# Microcrontroller.net
KiCad netlist of a schematic drawn in Altium Designer
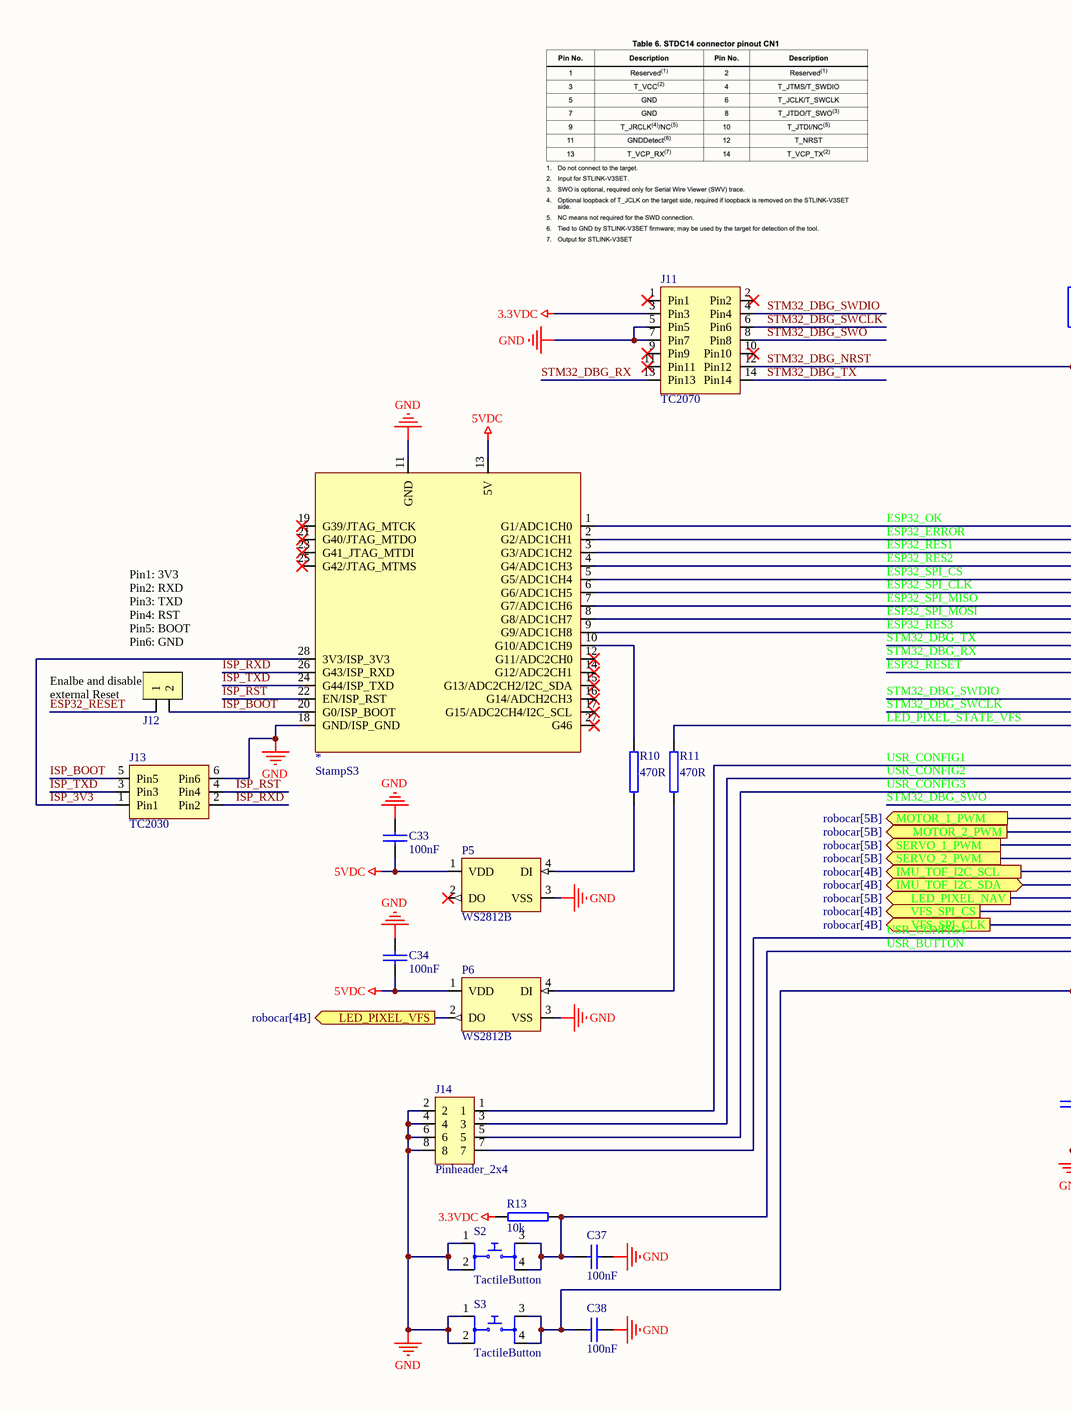
[diagram p0: Microcrontroller.SchDoc, left]
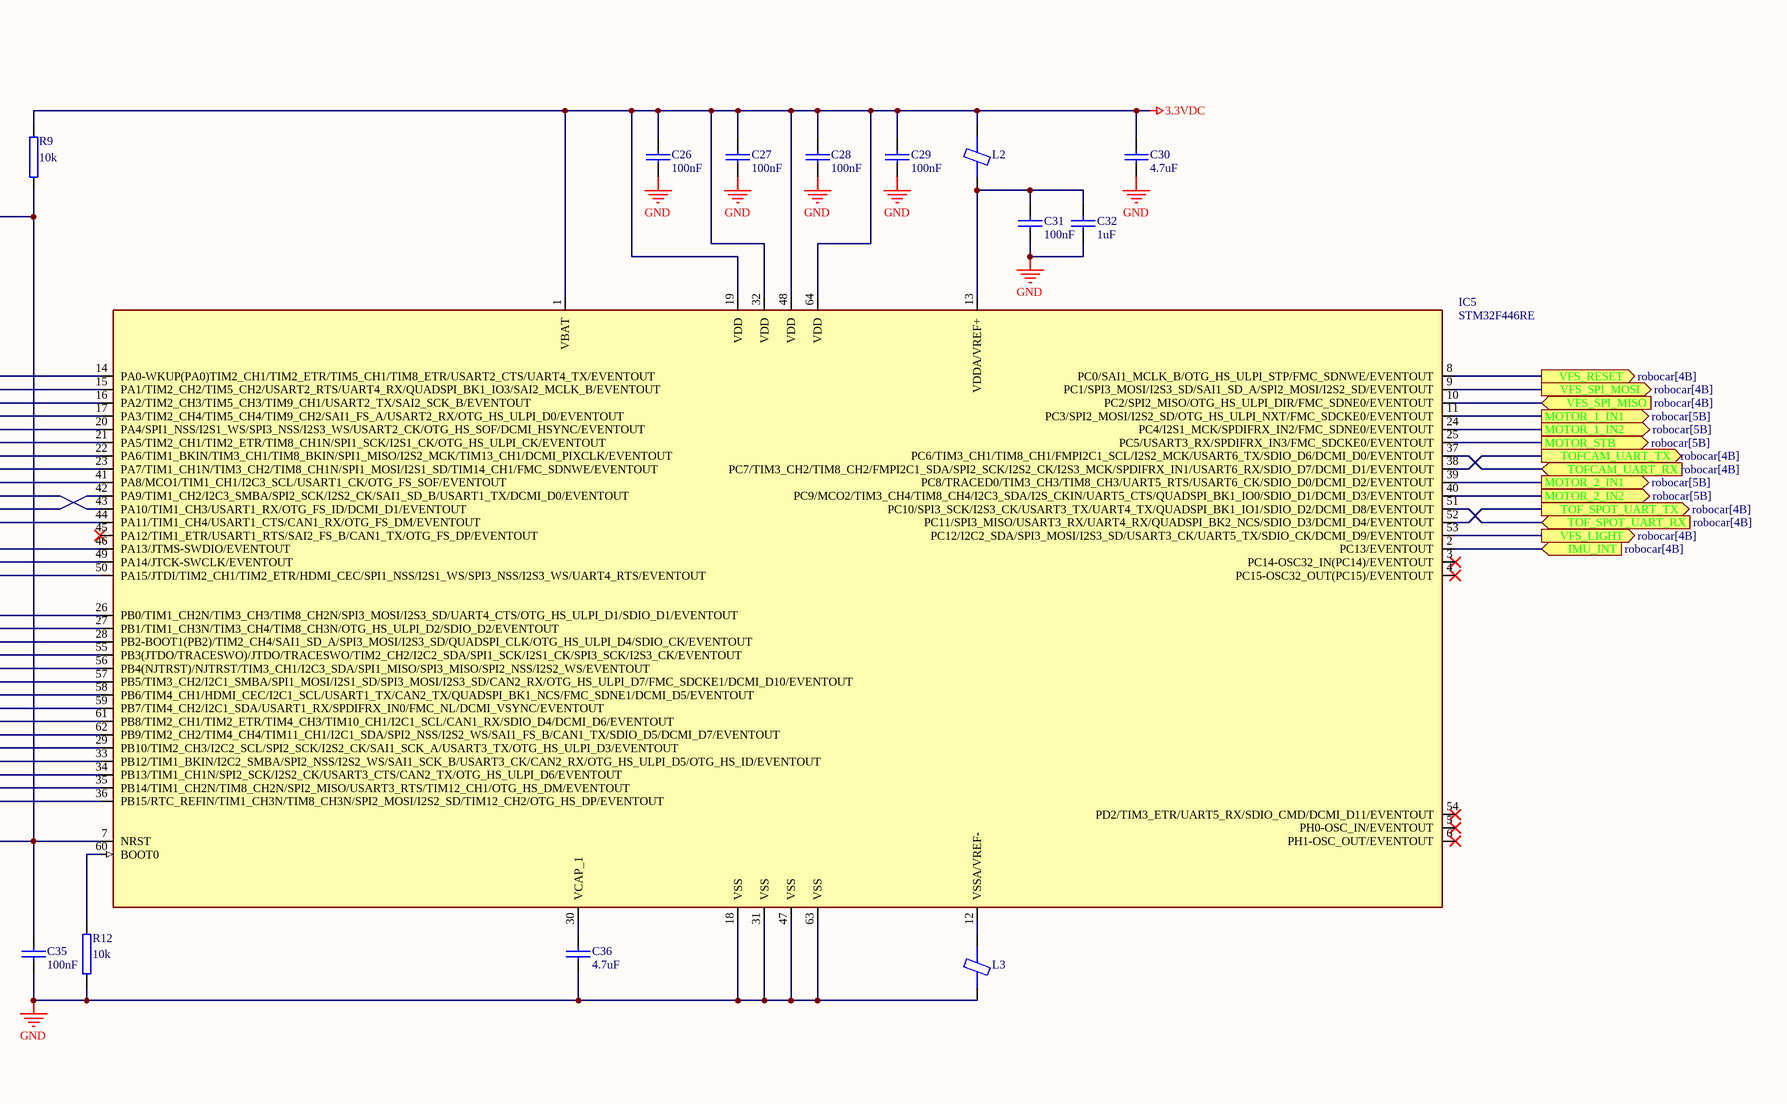
[diagram p1: Microcrontroller.SchDoc, right]

(export (version "E")
  (design (tool "Eeschema 10.0.6"))
  (components
    (comp (ref "*")
      (value "StampS3")
      (footprint "Stamp-S3-SMD")
      (libsource (lib "M5Stack_StampS3") (part "StampS3"))
    )
    (comp (ref "C26")
      (value "100nF")
      (footprint "0603")
      (fields
        (field (name "TOLERANCE") "-20%/+80%")
        (field (name "VOLTAGE") "50V")
        (field (name "Comment") "C 100nF 0603")
      )
      (libsource (lib "FHGR_Altium_database") (part "Capacitor"))
    )
    (comp (ref "C27")
      (value "100nF")
      (footprint "0603")
      (fields
        (field (name "TOLERANCE") "-20%/+80%")
        (field (name "VOLTAGE") "50V")
        (field (name "Comment") "C 100nF 0603")
      )
      (libsource (lib "FHGR_Altium_database") (part "Capacitor"))
    )
    (comp (ref "C28")
      (value "100nF")
      (footprint "0603")
      (fields
        (field (name "TOLERANCE") "-20%/+80%")
        (field (name "VOLTAGE") "50V")
        (field (name "Comment") "C 100nF 0603")
      )
      (libsource (lib "FHGR_Altium_database") (part "Capacitor"))
    )
    (comp (ref "C29")
      (value "100nF")
      (footprint "0603")
      (fields
        (field (name "TOLERANCE") "-20%/+80%")
        (field (name "VOLTAGE") "50V")
        (field (name "Comment") "C 100nF 0603")
      )
      (libsource (lib "FHGR_Altium_database") (part "Capacitor"))
    )
    (comp (ref "C30")
      (value "4.7uF")
      (footprint "0603")
      (fields
        (field (name "TOLERANCE") "10%")
        (field (name "VOLTAGE") "6.3V")
        (field (name "Comment") "C 4.7uF 0603")
      )
      (libsource (lib "FHGR_Altium_database") (part "Capacitor"))
    )
    (comp (ref "C31")
      (value "100nF")
      (footprint "0603")
      (fields
        (field (name "TOLERANCE") "-20%/+80%")
        (field (name "VOLTAGE") "50V")
        (field (name "Comment") "C 100nF 0603")
      )
      (libsource (lib "FHGR_Altium_database") (part "Capacitor"))
    )
    (comp (ref "C32")
      (value "1uF")
      (footprint "0603")
      (fields
        (field (name "TOLERANCE") "10%")
        (field (name "VOLTAGE") "25V")
        (field (name "Comment") "C 1uF 0603")
      )
      (libsource (lib "FHGR_Altium_database") (part "Capacitor"))
    )
    (comp (ref "C33")
      (value "100nF")
      (footprint "0603")
      (fields
        (field (name "TOLERANCE") "-20%/+80%")
        (field (name "VOLTAGE") "50V")
        (field (name "Comment") "C 100nF 0603")
      )
      (libsource (lib "FHGR_Altium_database") (part "Capacitor"))
    )
    (comp (ref "C34")
      (value "100nF")
      (footprint "0603")
      (fields
        (field (name "TOLERANCE") "-20%/+80%")
        (field (name "VOLTAGE") "50V")
        (field (name "Comment") "C 100nF 0603")
      )
      (libsource (lib "FHGR_Altium_database") (part "Capacitor"))
    )
    (comp (ref "C35")
      (value "100nF")
      (footprint "0603")
      (fields
        (field (name "TOLERANCE") "-20%/+80%")
        (field (name "VOLTAGE") "50V")
        (field (name "Comment") "C 100nF 0603")
      )
      (libsource (lib "FHGR_Altium_database") (part "Capacitor"))
    )
    (comp (ref "C36")
      (value "4.7uF")
      (footprint "0603")
      (fields
        (field (name "TOLERANCE") "10%")
        (field (name "VOLTAGE") "6.3V")
        (field (name "Comment") "C 4.7uF 0603")
      )
      (libsource (lib "FHGR_Altium_database") (part "Capacitor"))
    )
    (comp (ref "C37")
      (value "100nF")
      (footprint "0603")
      (fields
        (field (name "TOLERANCE") "-20%/+80%")
        (field (name "VOLTAGE") "50V")
        (field (name "Comment") "C 100nF 0603")
      )
      (libsource (lib "FHGR_Altium_database") (part "Capacitor"))
    )
    (comp (ref "C38")
      (value "100nF")
      (footprint "0603")
      (fields
        (field (name "TOLERANCE") "-20%/+80%")
        (field (name "VOLTAGE") "50V")
        (field (name "Comment") "C 100nF 0603")
      )
      (libsource (lib "FHGR_Altium_database") (part "Capacitor"))
    )
    (comp (ref "IC5")
      (value "STM32F446RE")
      (footprint "STM32F446RET6")
      (libsource (lib "STM32F446RE") (part "STM32F446RE"))
    )
    (comp (ref "J11") (value "TC2070") (footprint "TC2070") (libsource (lib "Tag-Connect") (part "TC2070")))
    (comp (ref "J12")
      (value "2Pin_Male")
      (footprint "Header1x2_254")
      (libsource (lib "FHGR_Altium_database") (part "Connector2Pin"))
    )
    (comp (ref "J13") (value "TC2030") (footprint "TC2030") (libsource (lib "Tag-Connect") (part "TC2030")))
    (comp (ref "J14")
      (value "Pinheader_2x4")
      (footprint "61300821121")
      (libsource (lib "util") (part "Pinheader_2x4"))
    )
    (comp (ref "L2")
      (value "L Ferrit Bead")
      (footprint "0805")
      (libsource (lib "FHGR_Altium_database") (part "Bead"))
    )
    (comp (ref "L3")
      (value "L Ferrit Bead")
      (footprint "0805")
      (libsource (lib "FHGR_Altium_database") (part "Bead"))
    )
    (comp (ref "P5")
      (value "WS2812B")
      (footprint "WS2812B_SMD")
      (libsource (lib "NeoPixel") (part "WS2812B"))
    )
    (comp (ref "P6")
      (value "WS2812B")
      (footprint "WS2812B_SMD")
      (libsource (lib "NeoPixel") (part "WS2812B"))
    )
    (comp (ref "R9")
      (value "10k")
      (footprint "0805")
      (fields (field (name "TOLERANCE") "1%") (field (name "Comment") "R 10K 0805"))
      (libsource (lib "FHGR_Altium_database") (part "Resistor"))
    )
    (comp (ref "R10")
      (value "470R")
      (footprint "0805")
      (fields (field (name "TOLERANCE") "1%") (field (name "Comment") "R 220R 0805"))
      (libsource (lib "FHGR_Altium_database") (part "Resistor"))
    )
    (comp (ref "R11")
      (value "470R")
      (footprint "0805")
      (fields (field (name "TOLERANCE") "1%") (field (name "Comment") "R 220R 0805"))
      (libsource (lib "FHGR_Altium_database") (part "Resistor"))
    )
    (comp (ref "R12")
      (value "10k")
      (footprint "0805")
      (fields (field (name "TOLERANCE") "1%") (field (name "Comment") "R 10K 0805"))
      (libsource (lib "FHGR_Altium_database") (part "Resistor"))
    )
    (comp (ref "R13")
      (value "10k")
      (footprint "0805")
      (fields (field (name "TOLERANCE") "1%") (field (name "Comment") "R 10K 0805"))
      (libsource (lib "FHGR_Altium_database") (part "Resistor"))
    )
    (comp (ref "S2")
      (value "TactileButton")
      (footprint "TactileButton-6x6mm")
      (fields (field (name "VOLTAGE") "12V"))
      (libsource (lib "FHGR_Altium_database") (part "Switch_Press_Button_4PIN"))
    )
    (comp (ref "S3")
      (value "TactileButton")
      (footprint "TactileButton-6x6mm")
      (fields (field (name "VOLTAGE") "12V"))
      (libsource (lib "FHGR_Altium_database") (part "Switch_Press_Button_4PIN"))
    )
  )
  (nets
    (net (code "1") (name "/ESP32_ERROR") (class "Default")
      (node (ref "*") (pin "2") (pinfunction "G2/ADC1CH1_2") (pintype "passive"))
      (node (ref "IC5") (pin "15") (pinfunction "PA1/TIM2_CH2/TIM5_CH2/USART2_RTS/UART4_RX/QUADSPI_BK1_IO3/SAI2_MCLK_B/EVENTOUT_15") (pintype "bidirectional"))
    )
    (net (code "2") (name "/ESP32_OK") (class "Default")
      (node (ref "*") (pin "1") (pinfunction "G1/ADC1CH0_1") (pintype "passive"))
      (node (ref "IC5") (pin "14") (pinfunction "PA0-WKUP(PA0)TIM2_CH1/TIM2_ETR/TIM5_CH1/TIM8_ETR/USART2_CTS/UART4_TX/EVENTOUT_14") (pintype "bidirectional"))
    )
    (net (code "3") (name "/ESP32_RES1") (class "Default")
      (node (ref "*") (pin "3") (pinfunction "G3/ADC1CH2_3") (pintype "passive"))
      (node (ref "IC5") (pin "16") (pinfunction "PA2/TIM2_CH3/TIM5_CH3/TIM9_CH1/USART2_TX/SAI2_SCK_B/EVENTOUT_16") (pintype "bidirectional"))
    )
    (net (code "4") (name "/ESP32_RES2") (class "Default")
      (node (ref "*") (pin "4") (pinfunction "G4/ADC1CH3_4") (pintype "passive"))
      (node (ref "IC5") (pin "17") (pinfunction "PA3/TIM2_CH4/TIM5_CH4/TIM9_CH2/SAI1_FS_A/USART2_RX/OTG_HS_ULPI_D0/EVENTOUT_17") (pintype "bidirectional"))
    )
    (net (code "5") (name "/ESP32_RES3") (class "Default")
      (node (ref "*") (pin "9") (pinfunction "G9/ADC1CH8_9") (pintype "passive"))
      (node (ref "IC5") (pin "41") (pinfunction "PA8/MCO1/TIM1_CH1/I2C3_SCL/USART1_CK/OTG_FS_SOF/EVENTOUT_41") (pintype "bidirectional"))
    )
    (net (code "6") (name "/ESP32_RESET") (class "Default")
      (node (ref "IC5") (pin "44") (pinfunction "PA11/TIM1_CH4/USART1_CTS/CAN1_RX/OTG_FS_DM/EVENTOUT_44") (pintype "bidirectional"))
      (node (ref "J12") (pin "1") (pinfunction "1_1") (pintype "passive"))
    )
    (net (code "7") (name "/ESP32_SPI_CLK") (class "Default")
      (node (ref "*") (pin "6") (pinfunction "G6/ADC1CH5_6") (pintype "passive"))
      (node (ref "IC5") (pin "21") (pinfunction "PA5/TIM2_CH1/TIM2_ETR/TIM8_CH1N/SPI1_SCK/I2S1_CK/OTG_HS_ULPI_CK/EVENTOUT_21") (pintype "bidirectional"))
    )
    (net (code "8") (name "/ESP32_SPI_CS") (class "Default")
      (node (ref "*") (pin "5") (pinfunction "G5/ADC1CH4_5") (pintype "passive"))
      (node (ref "IC5") (pin "20") (pinfunction "PA4/SPI1_NSS/I2S1_WS/SPI3_NSS/I2S3_WS/USART2_CK/OTG_HS_SOF/DCMI_HSYNC/EVENTOUT_20") (pintype "bidirectional"))
    )
    (net (code "9") (name "/ESP32_SPI_MISO") (class "Default")
      (node (ref "*") (pin "7") (pinfunction "G7/ADC1CH6_7") (pintype "passive"))
      (node (ref "IC5") (pin "22") (pinfunction "PA6/TIM1_BKIN/TIM3_CH1/TIM8_BKIN/SPI1_MISO/I2S2_MCK/TIM13_CH1/DCMI_PIXCLK/EVENTOUT_22") (pintype "bidirectional"))
    )
    (net (code "10") (name "/ESP32_SPI_MOSI") (class "Default")
      (node (ref "*") (pin "8") (pinfunction "G8/ADC1CH7_8") (pintype "passive"))
      (node (ref "IC5") (pin "23") (pinfunction "PA7/TIM1_CH1N/TIM3_CH2/TIM8_CH1N/SPI1_MOSI/I2S1_SD/TIM14_CH1/FMC_SDNWE/EVENTOUT_23") (pintype "bidirectional"))
    )
    (net (code "11") (name "/IMU_INT") (class "Default")
      (node (ref "IC5") (pin "2") (pinfunction "PC13/EVENTOUT_2") (pintype "bidirectional"))
    )
    (net (code "12") (name "/IMU_TOF_I2C_SCL") (class "Default")
      (node (ref "IC5") (pin "61") (pinfunction "PB8/TIM2_CH1/TIM2_ETR/TIM4_CH3/TIM10_CH1/I2C1_SCL/CAN1_RX/SDIO_D4/DCMI_D6/EVENTOUT_61") (pintype "bidirectional"))
    )
    (net (code "13") (name "/IMU_TOF_I2C_SDA") (class "Default")
      (node (ref "IC5") (pin "62") (pinfunction "PB9/TIM2_CH2/TIM4_CH4/TIM11_CH1/I2C1_SDA/SPI2_NSS/I2S2_WS/SAI1_FS_B/CAN1_TX/SDIO_D5/DCMI_D7/EVENTOUT_62") (pintype "bidirectional"))
    )
    (net (code "14") (name "/ISP_3V3") (class "Default")
      (node (ref "*") (pin "28") (pinfunction "3V3/ISP_3V3_28") (pintype "passive"))
      (node (ref "J13") (pin "1") (pinfunction "Pin1_1") (pintype "passive"))
    )
    (net (code "15") (name "/ISP_BOOT") (class "Default")
      (node (ref "*") (pin "20") (pinfunction "G0/ISP_BOOT_20") (pintype "passive"))
      (node (ref "J12") (pin "2") (pinfunction "2_2") (pintype "passive"))
      (node (ref "J13") (pin "5") (pinfunction "Pin5_5") (pintype "passive"))
    )
    (net (code "16") (name "/ISP_RST") (class "Default")
      (node (ref "*") (pin "22") (pinfunction "EN/ISP_RST_22") (pintype "passive"))
      (node (ref "J13") (pin "4") (pinfunction "Pin4_4") (pintype "passive"))
    )
    (net (code "17") (name "/ISP_RXD") (class "Default")
      (node (ref "*") (pin "26") (pinfunction "G43/ISP_RXD_26") (pintype "passive"))
      (node (ref "J13") (pin "2") (pinfunction "Pin2_2") (pintype "passive"))
    )
    (net (code "18") (name "/ISP_TXD") (class "Default")
      (node (ref "*") (pin "24") (pinfunction "G44/ISP_TXD_24") (pintype "passive"))
      (node (ref "J13") (pin "3") (pinfunction "Pin3_3") (pintype "passive"))
    )
    (net (code "19") (name "/LED_PIXEL_NAV") (class "Default")
      (node (ref "IC5") (pin "29") (pinfunction "PB10/TIM2_CH3/I2C2_SCL/SPI2_SCK/I2S2_CK/SAI1_SCK_A/USART3_TX/OTG_HS_ULPI_D3/EVENTOUT_29") (pintype "bidirectional"))
    )
    (net (code "20") (name "/LED_PIXEL_STATE_VFS") (class "Default")
      (node (ref "IC5") (pin "50") (pinfunction "PA15/JTDI/TIM2_CH1/TIM2_ETR/HDMI_CEC/SPI1_NSS/I2S1_WS/SPI3_NSS/I2S3_WS/UART4_RTS/EVENTOUT_50") (pintype "bidirectional"))
      (node (ref "R11") (pin "2") (pintype "passive"))
    )
    (net (code "21") (name "/LED_PIXEL_VFS") (class "Default")
      (node (ref "P6") (pin "2") (pinfunction "DO_2") (pintype "output"))
    )
    (net (code "22") (name "/MOTOR_1_IN1") (class "Default")
      (node (ref "IC5") (pin "11") (pinfunction "PC3/SPI2_MOSI/I2S2_SD/OTG_HS_ULPI_NXT/FMC_SDCKE0/EVENTOUT_11") (pintype "bidirectional"))
    )
    (net (code "23") (name "/MOTOR_1_IN2") (class "Default")
      (node (ref "IC5") (pin "24") (pinfunction "PC4/I2S1_MCK/SPDIFRX_IN2/FMC_SDNE0/EVENTOUT_24") (pintype "bidirectional"))
    )
    (net (code "24") (name "/MOTOR_1_PWM") (class "Default")
      (node (ref "IC5") (pin "56") (pinfunction "PB4(NJTRST)/NJTRST/TIM3_CH1/I2C3_SDA/SPI1_MISO/SPI3_MISO/SPI2_NSS/I2S2_WS/EVENTOUT_56") (pintype "bidirectional"))
    )
    (net (code "25") (name "/MOTOR_2_IN1") (class "Default")
      (node (ref "IC5") (pin "39") (pinfunction "PC8/TRACED0/TIM3_CH3/TIM8_CH3/UART5_RTS/USART6_CK/SDIO_D0/DCMI_D2/EVENTOUT_39") (pintype "bidirectional"))
    )
    (net (code "26") (name "/MOTOR_2_IN2") (class "Default")
      (node (ref "IC5") (pin "40") (pinfunction "PC9/MCO2/TIM3_CH4/TIM8_CH4/I2C3_SDA/I2S_CKIN/UART5_CTS/QUADSPI_BK1_IO0/SDIO_D1/DCMI_D3/EVENTOUT_40") (pintype "bidirectional"))
    )
    (net (code "27") (name "/MOTOR_2_PWM") (class "Default")
      (node (ref "IC5") (pin "57") (pinfunction "PB5/TIM3_CH2/I2C1_SMBA/SPI1_MOSI/I2S1_SD/SPI3_MOSI/I2S3_SD/CAN2_RX/OTG_HS_ULPI_D7/FMC_SDCKE1/DCMI_D10/EVENTOUT_57") (pintype "bidirectional"))
    )
    (net (code "28") (name "/MOTOR_STB") (class "Default")
      (node (ref "IC5") (pin "25") (pinfunction "PC5/USART3_RX/SPDIFRX_IN3/FMC_SDCKE0/EVENTOUT_25") (pintype "bidirectional"))
    )
    (net (code "29") (name "/SERVO_1_PWM") (class "Default")
      (node (ref "IC5") (pin "58") (pinfunction "PB6/TIM4_CH1/HDMI_CEC/I2C1_SCL/USART1_TX/CAN2_TX/QUADSPI_BK1_NCS/FMC_SDNE1/DCMI_D5/EVENTOUT_58") (pintype "bidirectional"))
    )
    (net (code "30") (name "/SERVO_2_PWM") (class "Default")
      (node (ref "IC5") (pin "59") (pinfunction "PB7/TIM4_CH2/I2C1_SDA/USART1_RX/SPDIFRX_IN0/FMC_NL/DCMI_VSYNC/EVENTOUT_59") (pintype "bidirectional"))
    )
    (net (code "31") (name "/STM32_DBG_NRST") (class "Default")
      (node (ref "C35") (pin "1") (pintype "passive"))
      (node (ref "C38") (pin "2") (pintype "passive"))
      (node (ref "IC5") (pin "7") (pinfunction "NRST_7") (pintype "bidirectional"))
      (node (ref "J11") (pin "12") (pinfunction "Pin12_12") (pintype "passive"))
      (node (ref "R9") (pin "1") (pintype "passive"))
      (node (ref "S3") (pin "3") (pintype "passive"))
      (node (ref "S3") (pin "4") (pintype "passive"))
    )
    (net (code "32") (name "/STM32_DBG_RX") (class "Default")
      (node (ref "IC5") (pin "42") (pinfunction "PA9/TIM1_CH2/I2C3_SMBA/SPI2_SCK/I2S2_CK/SAI1_SD_B/USART1_TX/DCMI_D0/EVENTOUT_42") (pintype "bidirectional"))
      (node (ref "J11") (pin "13") (pinfunction "Pin13_13") (pintype "passive"))
    )
    (net (code "33") (name "/STM32_DBG_SWCLK") (class "Default")
      (node (ref "IC5") (pin "49") (pinfunction "PA14/JTCK-SWCLK/EVENTOUT_49") (pintype "bidirectional"))
      (node (ref "J11") (pin "6") (pinfunction "Pin6_6") (pintype "passive"))
    )
    (net (code "34") (name "/STM32_DBG_SWDIO") (class "Default")
      (node (ref "IC5") (pin "46") (pinfunction "PA13/JTMS-SWDIO/EVENTOUT_46") (pintype "bidirectional"))
      (node (ref "J11") (pin "4") (pinfunction "Pin4_4") (pintype "passive"))
    )
    (net (code "35") (name "/STM32_DBG_SWO") (class "Default")
      (node (ref "IC5") (pin "55") (pinfunction "PB3(JTDO/TRACESWO)/JTDO/TRACESWO/TIM2_CH2/I2C2_SDA/SPI1_SCK/I2S1_CK/SPI3_SCK/I2S3_CK/EVENTOUT_55") (pintype "bidirectional"))
      (node (ref "J11") (pin "8") (pinfunction "Pin8_8") (pintype "passive"))
    )
    (net (code "36") (name "/STM32_DBG_TX") (class "Default")
      (node (ref "IC5") (pin "43") (pinfunction "PA10/TIM1_CH3/USART1_RX/OTG_FS_ID/DCMI_D1/EVENTOUT_43") (pintype "bidirectional"))
      (node (ref "J11") (pin "14") (pinfunction "Pin14_14") (pintype "passive"))
    )
    (net (code "37") (name "/TOFCAM_UART_RX") (class "Default")
      (node (ref "IC5") (pin "37") (pinfunction "PC6/TIM3_CH1/TIM8_CH1/FMPI2C1_SCL/I2S2_MCK/USART6_TX/SDIO_D6/DCMI_D0/EVENTOUT_37") (pintype "bidirectional"))
    )
    (net (code "38") (name "/TOFCAM_UART_TX") (class "Default")
      (node (ref "IC5") (pin "38") (pinfunction "PC7/TIM3_CH2/TIM8_CH2/FMPI2C1_SDA/SPI2_SCK/I2S2_CK/I2S3_MCK/SPDIFRX_IN1/USART6_RX/SDIO_D7/DCMI_D1/EVENTOUT_38") (pintype "bidirectional"))
    )
    (net (code "39") (name "/TOF_SPOT_UART_RX") (class "Default")
      (node (ref "IC5") (pin "51") (pinfunction "PC10/SPI3_SCK/I2S3_CK/USART3_TX/UART4_TX/QUADSPI_BK1_IO1/SDIO_D2/DCMI_D8/EVENTOUT_51") (pintype "bidirectional"))
    )
    (net (code "40") (name "/TOF_SPOT_UART_TX") (class "Default")
      (node (ref "IC5") (pin "52") (pinfunction "PC11/SPI3_MISO/USART3_RX/UART4_RX/QUADSPI_BK2_NCS/SDIO_D3/DCMI_D4/EVENTOUT_52") (pintype "bidirectional"))
    )
    (net (code "41") (name "/USR_BUTTON") (class "Default")
      (node (ref "C37") (pin "2") (pintype "passive"))
      (node (ref "IC5") (pin "36") (pinfunction "PB15/RTC_REFIN/TIM1_CH3N/TIM8_CH3N/SPI2_MOSI/I2S2_SD/TIM12_CH2/OTG_HS_DP/EVENTOUT_36") (pintype "bidirectional"))
      (node (ref "R13") (pin "1") (pintype "passive"))
      (node (ref "S2") (pin "3") (pintype "passive"))
      (node (ref "S2") (pin "4") (pintype "passive"))
    )
    (net (code "42") (name "/USR_CONFIG1") (class "Default")
      (node (ref "IC5") (pin "26") (pinfunction "PB0/TIM1_CH2N/TIM3_CH3/TIM8_CH2N/SPI3_MOSI/I2S3_SD/UART4_CTS/OTG_HS_ULPI_D1/SDIO_D1/EVENTOUT_26") (pintype "bidirectional"))
      (node (ref "J14") (pin "1") (pinfunction "1_1") (pintype "passive"))
    )
    (net (code "43") (name "/USR_CONFIG2") (class "Default")
      (node (ref "IC5") (pin "27") (pinfunction "PB1/TIM1_CH3N/TIM3_CH4/TIM8_CH3N/OTG_HS_ULPI_D2/SDIO_D2/EVENTOUT_27") (pintype "bidirectional"))
      (node (ref "J14") (pin "3") (pinfunction "3_3") (pintype "passive"))
    )
    (net (code "44") (name "/USR_CONFIG3") (class "Default")
      (node (ref "IC5") (pin "28") (pinfunction "PB2-BOOT1(PB2)/TIM2_CH4/SAI1_SD_A/SPI3_MOSI/I2S3_SD/QUADSPI_CLK/OTG_HS_ULPI_D4/SDIO_CK/EVENTOUT_28") (pintype "bidirectional"))
      (node (ref "J14") (pin "5") (pinfunction "5_5") (pintype "passive"))
    )
    (net (code "45") (name "/USR_CONFIG4") (class "Default")
      (node (ref "IC5") (pin "35") (pinfunction "PB14/TIM1_CH2N/TIM8_CH2N/SPI2_MISO/USART3_RTS/TIM12_CH1/OTG_HS_DM/EVENTOUT_35") (pintype "bidirectional"))
      (node (ref "J14") (pin "7") (pinfunction "7_7") (pintype "passive"))
    )
    (net (code "46") (name "/VFS_LIGHT") (class "Default")
      (node (ref "IC5") (pin "53") (pinfunction "PC12/I2C2_SDA/SPI3_MOSI/I2S3_SD/USART3_CK/UART5_TX/SDIO_CK/DCMI_D9/EVENTOUT_53") (pintype "bidirectional"))
    )
    (net (code "47") (name "/VFS_RESET") (class "Default")
      (node (ref "IC5") (pin "8") (pinfunction "PC0/SAI1_MCLK_B/OTG_HS_ULPI_STP/FMC_SDNWE/EVENTOUT_8") (pintype "bidirectional"))
    )
    (net (code "48") (name "/VFS_SPI_CLK") (class "Default")
      (node (ref "IC5") (pin "34") (pinfunction "PB13/TIM1_CH1N/SPI2_SCK/I2S2_CK/USART3_CTS/CAN2_TX/OTG_HS_ULPI_D6/EVENTOUT_34") (pintype "bidirectional"))
    )
    (net (code "49") (name "/VFS_SPI_CS") (class "Default")
      (node (ref "IC5") (pin "33") (pinfunction "PB12/TIM1_BKIN/I2C2_SMBA/SPI2_NSS/I2S2_WS/SAI1_SCK_B/USART3_CK/CAN2_RX/OTG_HS_ULPI_D5/OTG_HS_ID/EVENTOUT_33") (pintype "bidirectional"))
    )
    (net (code "50") (name "/VFS_SPI_MISO") (class "Default")
      (node (ref "IC5") (pin "10") (pinfunction "PC2/SPI2_MISO/OTG_HS_ULPI_DIR/FMC_SDNE0/EVENTOUT_10") (pintype "bidirectional"))
    )
    (net (code "51") (name "/VFS_SPI_MOSI") (class "Default")
      (node (ref "IC5") (pin "9") (pinfunction "PC1/SPI3_MOSI/I2S3_SD/SAI1_SD_A/SPI2_MOSI/I2S2_SD/EVENTOUT_9") (pintype "bidirectional"))
    )
    (net (code "52") (name "3.3VDC") (class "Default")
      (node (ref "C26") (pin "1") (pintype "passive"))
      (node (ref "C27") (pin "1") (pintype "passive"))
      (node (ref "C28") (pin "1") (pintype "passive"))
      (node (ref "C29") (pin "1") (pintype "passive"))
      (node (ref "C30") (pin "1") (pintype "passive"))
      (node (ref "IC5") (pin "1") (pinfunction "VBAT_1") (pintype "power_in"))
      (node (ref "IC5") (pin "19") (pinfunction "VDD_19") (pintype "power_in"))
      (node (ref "IC5") (pin "32") (pinfunction "VDD_32") (pintype "power_in"))
      (node (ref "IC5") (pin "48") (pinfunction "VDD_48") (pintype "power_in"))
      (node (ref "IC5") (pin "64") (pinfunction "VDD_64") (pintype "power_in"))
      (node (ref "J11") (pin "3") (pinfunction "Pin3_3") (pintype "passive"))
      (node (ref "L2") (pin "2") (pintype "passive"))
      (node (ref "R13") (pin "2") (pintype "passive"))
      (node (ref "R9") (pin "2") (pintype "passive"))
    )
    (net (code "53") (name "5VDC") (class "Default")
      (node (ref "*") (pin "13") (pinfunction "5V_13") (pintype "passive"))
      (node (ref "C33") (pin "1") (pintype "passive"))
      (node (ref "C34") (pin "1") (pintype "passive"))
      (node (ref "P5") (pin "1") (pinfunction "VDD_1") (pintype "power_in"))
      (node (ref "P6") (pin "1") (pinfunction "VDD_1") (pintype "power_in"))
    )
    (net (code "54") (name "GND") (class "Default")
      (node (ref "*") (pin "11") (pinfunction "GND_11") (pintype "passive"))
      (node (ref "*") (pin "18") (pinfunction "GND/ISP_GND_18") (pintype "passive"))
      (node (ref "C26") (pin "2") (pintype "passive"))
      (node (ref "C27") (pin "2") (pintype "passive"))
      (node (ref "C28") (pin "2") (pintype "passive"))
      (node (ref "C29") (pin "2") (pintype "passive"))
      (node (ref "C30") (pin "2") (pintype "passive"))
      (node (ref "C31") (pin "2") (pintype "passive"))
      (node (ref "C32") (pin "2") (pintype "passive"))
      (node (ref "C33") (pin "2") (pintype "passive"))
      (node (ref "C34") (pin "2") (pintype "passive"))
      (node (ref "C35") (pin "2") (pintype "passive"))
      (node (ref "C36") (pin "2") (pintype "passive"))
      (node (ref "C37") (pin "1") (pintype "passive"))
      (node (ref "C38") (pin "1") (pintype "passive"))
      (node (ref "IC5") (pin "18") (pinfunction "VSS_18") (pintype "power_in"))
      (node (ref "IC5") (pin "31") (pinfunction "VSS_31") (pintype "power_in"))
      (node (ref "IC5") (pin "47") (pinfunction "VSS_47") (pintype "power_in"))
      (node (ref "IC5") (pin "63") (pinfunction "VSS_63") (pintype "power_in"))
      (node (ref "J11") (pin "5") (pinfunction "Pin5_5") (pintype "passive"))
      (node (ref "J11") (pin "7") (pinfunction "Pin7_7") (pintype "passive"))
      (node (ref "J13") (pin "6") (pinfunction "Pin6_6") (pintype "passive"))
      (node (ref "J14") (pin "2") (pinfunction "2_2") (pintype "passive"))
      (node (ref "J14") (pin "4") (pinfunction "4_4") (pintype "passive"))
      (node (ref "J14") (pin "6") (pinfunction "6_6") (pintype "passive"))
      (node (ref "J14") (pin "8") (pinfunction "8_8") (pintype "passive"))
      (node (ref "L3") (pin "2") (pintype "passive"))
      (node (ref "P5") (pin "3") (pinfunction "VSS_3") (pintype "power_in"))
      (node (ref "P6") (pin "3") (pinfunction "VSS_3") (pintype "power_in"))
      (node (ref "R12") (pin "2") (pintype "passive"))
      (node (ref "S2") (pin "1") (pintype "passive"))
      (node (ref "S2") (pin "2") (pintype "passive"))
      (node (ref "S3") (pin "1") (pintype "passive"))
      (node (ref "S3") (pin "2") (pintype "passive"))
    )
    (net (code "55") (name "Net-(*-G10{slash}ADC1CH9)") (class "Default")
      (node (ref "*") (pin "10") (pinfunction "G10/ADC1CH9_10") (pintype "passive"))
      (node (ref "R10") (pin "2") (pintype "passive"))
    )
    (net (code "56") (name "Net-(IC5-BOOT0)") (class "Default")
      (node (ref "IC5") (pin "60") (pinfunction "BOOT0_60") (pintype "input"))
      (node (ref "R12") (pin "1") (pintype "passive"))
    )
    (net (code "57") (name "Net-(IC5-VCAP_1)") (class "Default")
      (node (ref "C36") (pin "1") (pintype "passive"))
      (node (ref "IC5") (pin "30") (pinfunction "VCAP_1_30") (pintype "power_in"))
    )
    (net (code "58") (name "Net-(IC5-VDDA{slash}VREF+)") (class "Default")
      (node (ref "C31") (pin "1") (pintype "passive"))
      (node (ref "C32") (pin "1") (pintype "passive"))
      (node (ref "IC5") (pin "13") (pinfunction "VDDA/VREF+_13") (pintype "power_in"))
      (node (ref "L2") (pin "1") (pintype "passive"))
    )
    (net (code "59") (name "Net-(IC5-VSSA{slash}VREF-)") (class "Default")
      (node (ref "IC5") (pin "12") (pinfunction "VSSA/VREF-_12") (pintype "power_in"))
      (node (ref "L3") (pin "1") (pintype "passive"))
    )
    (net (code "60") (name "Net-(P5-DI)") (class "Default")
      (node (ref "P5") (pin "4") (pinfunction "DI_4") (pintype "input"))
      (node (ref "R10") (pin "1") (pintype "passive"))
    )
    (net (code "61") (name "Net-(P6-DI)") (class "Default")
      (node (ref "P6") (pin "4") (pinfunction "DI_4") (pintype "input"))
      (node (ref "R11") (pin "1") (pintype "passive"))
    )
    (net (code "62") (name "unconnected-(*-G11{slash}ADC2CH0-Pad12)") (class "Default")
      (node (ref "*") (pin "12") (pinfunction "G11/ADC2CH0_12") (pintype "passive+no_connect"))
    )
    (net (code "63") (name "unconnected-(*-G12{slash}ADC2CH1-Pad14)") (class "Default")
      (node (ref "*") (pin "14") (pinfunction "G12/ADC2CH1_14") (pintype "passive+no_connect"))
    )
    (net (code "64") (name "unconnected-(*-G13{slash}ADC2CH2{slash}I2C_SDA-Pad15)") (class "Default")
      (node (ref "*") (pin "15") (pinfunction "G13/ADC2CH2/I2C_SDA_15") (pintype "passive+no_connect"))
    )
    (net (code "65") (name "unconnected-(*-G14{slash}ADCH2CH3-Pad16)") (class "Default")
      (node (ref "*") (pin "16") (pinfunction "G14/ADCH2CH3_16") (pintype "passive+no_connect"))
    )
    (net (code "66") (name "unconnected-(*-G15{slash}ADC2CH4{slash}I2C_SCL-Pad17)") (class "Default")
      (node (ref "*") (pin "17") (pinfunction "G15/ADC2CH4/I2C_SCL_17") (pintype "passive+no_connect"))
    )
    (net (code "67") (name "unconnected-(*-G39{slash}JTAG_MTCK-Pad19)") (class "Default")
      (node (ref "*") (pin "19") (pinfunction "G39/JTAG_MTCK_19") (pintype "passive+no_connect"))
    )
    (net (code "68") (name "unconnected-(*-G40{slash}JTAG_MTDO-Pad21)") (class "Default")
      (node (ref "*") (pin "21") (pinfunction "G40/JTAG_MTDO_21") (pintype "passive+no_connect"))
    )
    (net (code "69") (name "unconnected-(*-G41_JTAG_MTDI-Pad23)") (class "Default")
      (node (ref "*") (pin "23") (pinfunction "G41_JTAG_MTDI_23") (pintype "passive+no_connect"))
    )
    (net (code "70") (name "unconnected-(*-G42{slash}JTAG_MTMS-Pad25)") (class "Default")
      (node (ref "*") (pin "25") (pinfunction "G42/JTAG_MTMS_25") (pintype "passive+no_connect"))
    )
    (net (code "71") (name "unconnected-(*-G46-Pad27)") (class "Default")
      (node (ref "*") (pin "27") (pinfunction "G46_27") (pintype "passive+no_connect"))
    )
    (net (code "72") (name "unconnected-(IC5-PA12{slash}TIM1_ETR{slash}USART1_RTS{slash}SAI2_FS_B{slash}CAN1_TX{slash}OTG_FS_DP{slash}EVENTOUT-Pad45)") (class "Default")
      (node (ref "IC5") (pin "45") (pinfunction "PA12/TIM1_ETR/USART1_RTS/SAI2_FS_B/CAN1_TX/OTG_FS_DP/EVENTOUT_45") (pintype "bidirectional+no_connect"))
    )
    (net (code "73") (name "unconnected-(IC5-PC14-OSC32_IN(PC14){slash}EVENTOUT-Pad3)") (class "Default")
      (node (ref "IC5") (pin "3") (pinfunction "PC14-OSC32_IN(PC14)/EVENTOUT_3") (pintype "bidirectional+no_connect"))
    )
    (net (code "74") (name "unconnected-(IC5-PC15-OSC32_OUT(PC15){slash}EVENTOUT-Pad4)") (class "Default")
      (node (ref "IC5") (pin "4") (pinfunction "PC15-OSC32_OUT(PC15)/EVENTOUT_4") (pintype "bidirectional+no_connect"))
    )
    (net (code "75") (name "unconnected-(IC5-PD2{slash}TIM3_ETR{slash}UART5_RX{slash}SDIO_CMD{slash}DCMI_D11{slash}EVENTOUT-Pad54)") (class "Default")
      (node (ref "IC5") (pin "54") (pinfunction "PD2/TIM3_ETR/UART5_RX/SDIO_CMD/DCMI_D11/EVENTOUT_54") (pintype "bidirectional+no_connect"))
    )
    (net (code "76") (name "unconnected-(IC5-PH0-OSC_IN{slash}EVENTOUT-Pad5)") (class "Default")
      (node (ref "IC5") (pin "5") (pinfunction "PH0-OSC_IN/EVENTOUT_5") (pintype "bidirectional+no_connect"))
    )
    (net (code "77") (name "unconnected-(IC5-PH1-OSC_OUT{slash}EVENTOUT-Pad6)") (class "Default")
      (node (ref "IC5") (pin "6") (pinfunction "PH1-OSC_OUT/EVENTOUT_6") (pintype "bidirectional+no_connect"))
    )
    (net (code "78") (name "unconnected-(J11-Pin1-Pad1)") (class "Default")
      (node (ref "J11") (pin "1") (pinfunction "Pin1_1") (pintype "passive+no_connect"))
    )
    (net (code "79") (name "unconnected-(J11-Pin2-Pad2)") (class "Default")
      (node (ref "J11") (pin "2") (pinfunction "Pin2_2") (pintype "passive+no_connect"))
    )
    (net (code "80") (name "unconnected-(J11-Pin9-Pad9)") (class "Default")
      (node (ref "J11") (pin "9") (pinfunction "Pin9_9") (pintype "passive+no_connect"))
    )
    (net (code "81") (name "unconnected-(J11-Pin10-Pad10)") (class "Default")
      (node (ref "J11") (pin "10") (pinfunction "Pin10_10") (pintype "passive+no_connect"))
    )
    (net (code "82") (name "unconnected-(J11-Pin11-Pad11)") (class "Default")
      (node (ref "J11") (pin "11") (pinfunction "Pin11_11") (pintype "passive+no_connect"))
    )
    (net (code "83") (name "unconnected-(P5-DO-Pad2)") (class "Default")
      (node (ref "P5") (pin "2") (pinfunction "DO_2") (pintype "output+no_connect"))
    )
  )
)
